# Attenuverting_Mixer_Slim_Front_Panel_v1.net
KiCad netlist of a schematic drawn in EAGLE
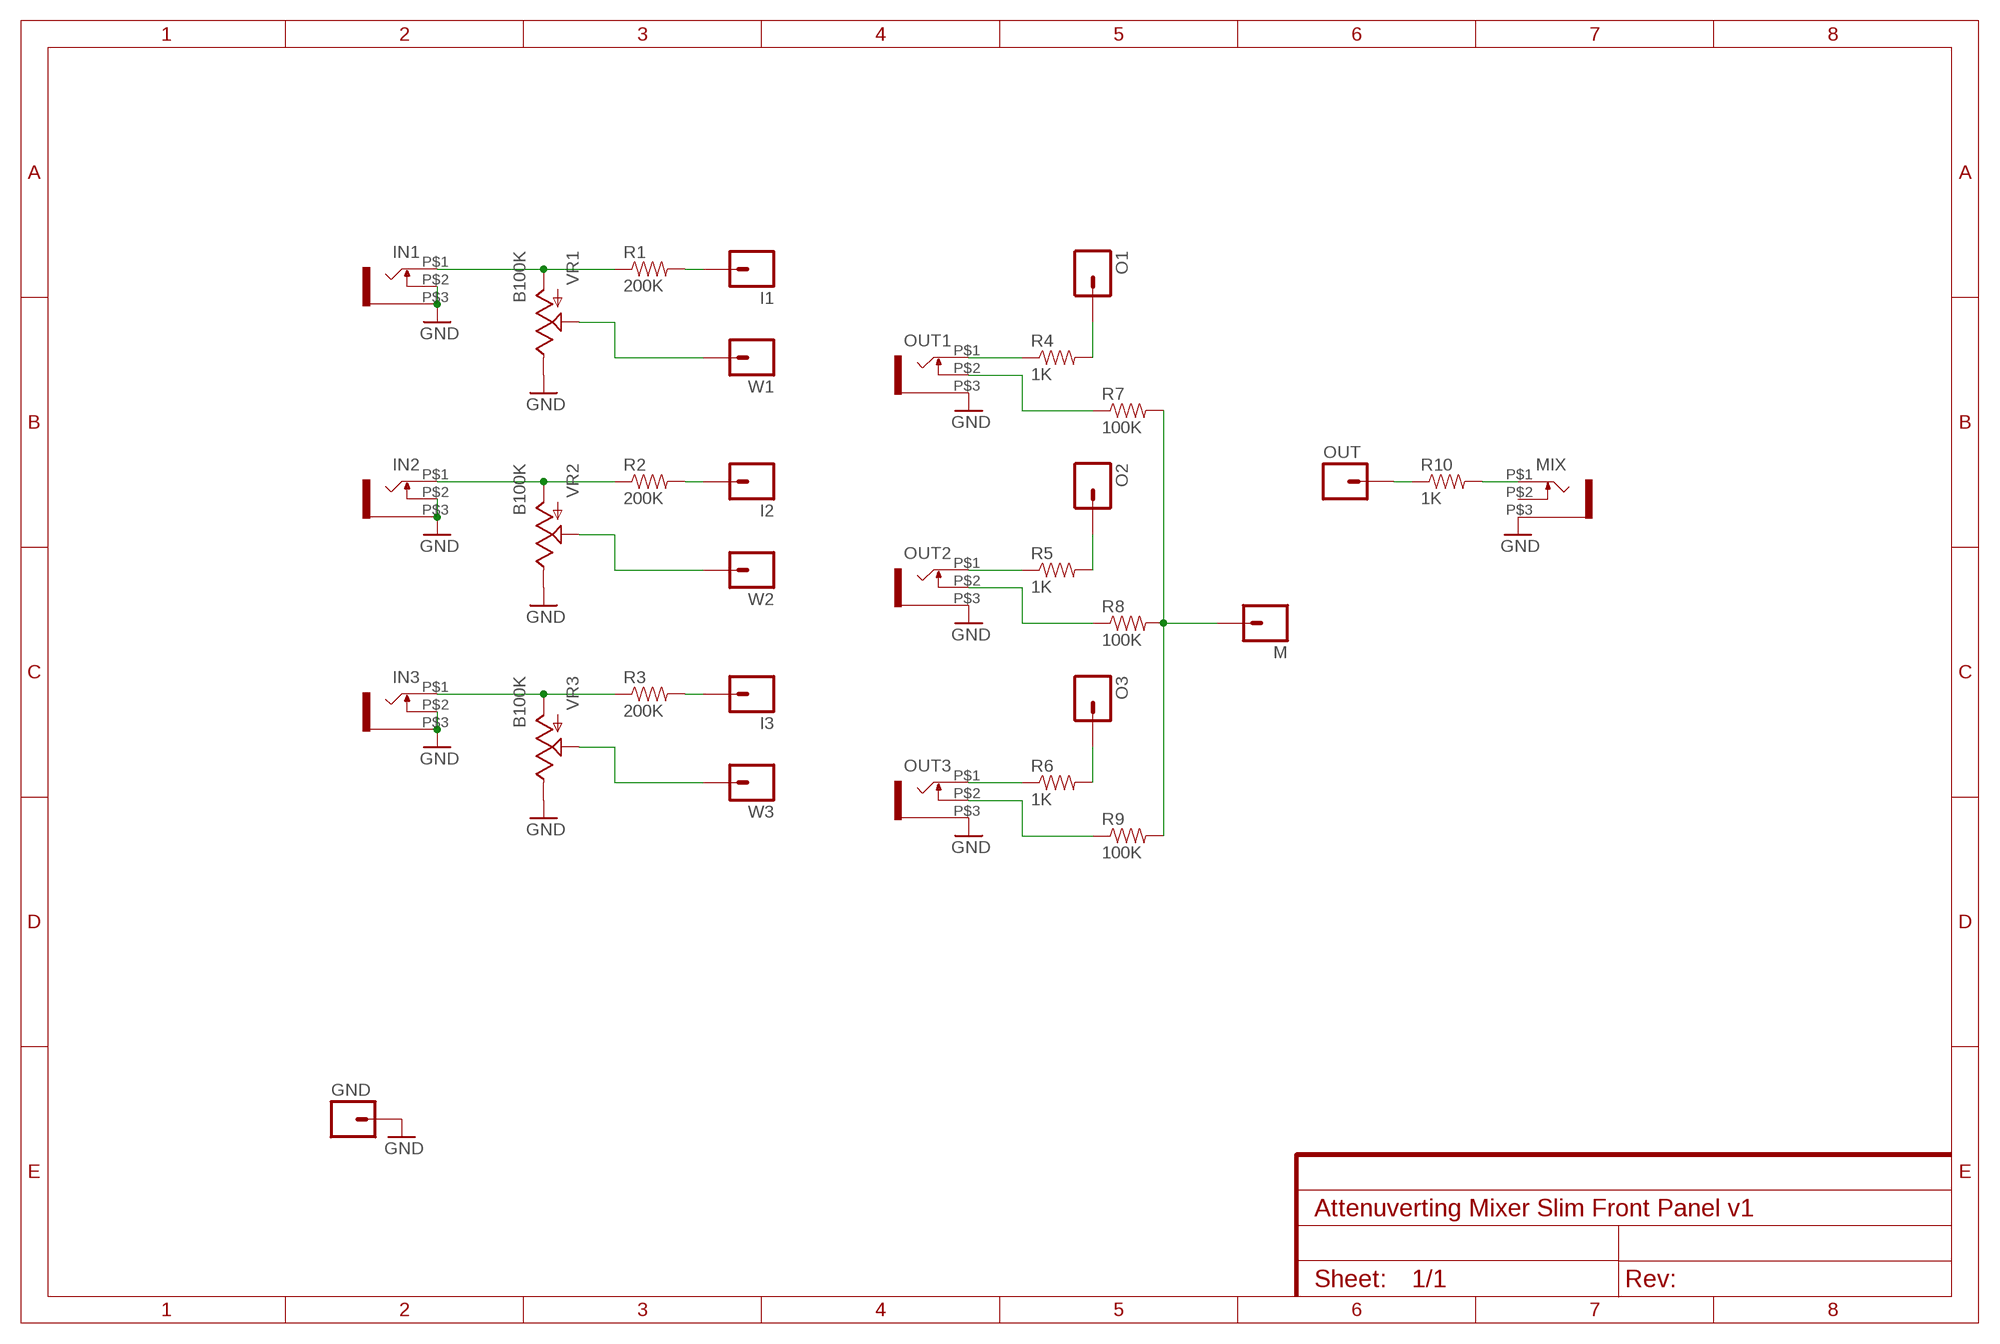
[diagram p0: schematic, sheet 1]

(export (version "E")
  (design (tool "Eeschema 10.0.6"))
  (components
    (comp (ref "GND")
      (value "M01PTH")
      (footprint "eagle-import:1X01")
      (libsource (lib "eagle-import") (part "M01PTH"))
    )
    (comp (ref "I1")
      (value "M01PTH")
      (footprint "eagle-import:1X01")
      (libsource (lib "eagle-import") (part "M01PTH"))
    )
    (comp (ref "I2")
      (value "M01PTH")
      (footprint "eagle-import:1X01")
      (libsource (lib "eagle-import") (part "M01PTH"))
    )
    (comp (ref "I3")
      (value "M01PTH")
      (footprint "eagle-import:1X01")
      (libsource (lib "eagle-import") (part "M01PTH"))
    )
    (comp (ref "IN1")
      (value "WQP-PJ301M-12_JACK")
      (footprint "eagle-import:WQP-PJ301M-12_JACK")
      (libsource (lib "eagle-import") (part "WQP-PJ301M-12_JACK"))
    )
    (comp (ref "IN2")
      (value "WQP-PJ301M-12_JACK")
      (footprint "eagle-import:WQP-PJ301M-12_JACK")
      (libsource (lib "eagle-import") (part "WQP-PJ301M-12_JACK"))
    )
    (comp (ref "IN3")
      (value "WQP-PJ301M-12_JACK")
      (footprint "eagle-import:WQP-PJ301M-12_JACK")
      (libsource (lib "eagle-import") (part "WQP-PJ301M-12_JACK"))
    )
    (comp (ref "M")
      (value "M01PTH")
      (footprint "eagle-import:1X01")
      (libsource (lib "eagle-import") (part "M01PTH"))
    )
    (comp (ref "MIX")
      (value "WQP-PJ301M-12_JACK")
      (footprint "eagle-import:WQP-PJ301M-12_JACK")
      (libsource (lib "eagle-import") (part "WQP-PJ301M-12_JACK"))
    )
    (comp (ref "O1")
      (value "M01PTH")
      (footprint "eagle-import:1X01")
      (libsource (lib "eagle-import") (part "M01PTH"))
    )
    (comp (ref "O2")
      (value "M01PTH")
      (footprint "eagle-import:1X01")
      (libsource (lib "eagle-import") (part "M01PTH"))
    )
    (comp (ref "O3")
      (value "M01PTH")
      (footprint "eagle-import:1X01")
      (libsource (lib "eagle-import") (part "M01PTH"))
    )
    (comp (ref "OUT")
      (value "M01PTH")
      (footprint "eagle-import:1X01")
      (libsource (lib "eagle-import") (part "M01PTH"))
    )
    (comp (ref "OUT1")
      (value "WQP-PJ301M-12_JACK")
      (footprint "eagle-import:WQP-PJ301M-12_JACK")
      (libsource (lib "eagle-import") (part "WQP-PJ301M-12_JACK"))
    )
    (comp (ref "OUT2")
      (value "WQP-PJ301M-12_JACK")
      (footprint "eagle-import:WQP-PJ301M-12_JACK")
      (libsource (lib "eagle-import") (part "WQP-PJ301M-12_JACK"))
    )
    (comp (ref "OUT3")
      (value "WQP-PJ301M-12_JACK")
      (footprint "eagle-import:WQP-PJ301M-12_JACK")
      (libsource (lib "eagle-import") (part "WQP-PJ301M-12_JACK"))
    )
    (comp (ref "R1")
      (value "200K")
      (footprint "eagle-import:0805")
      (libsource (lib "eagle-import") (part "RESISTOR0805-RES"))
    )
    (comp (ref "R2")
      (value "200K")
      (footprint "eagle-import:0805")
      (libsource (lib "eagle-import") (part "RESISTOR0805-RES"))
    )
    (comp (ref "R3")
      (value "200K")
      (footprint "eagle-import:0805")
      (libsource (lib "eagle-import") (part "RESISTOR0805-RES"))
    )
    (comp (ref "R4")
      (value "1K")
      (footprint "eagle-import:0805")
      (libsource (lib "eagle-import") (part "RESISTOR0805-RES"))
    )
    (comp (ref "R5")
      (value "1K")
      (footprint "eagle-import:0805")
      (libsource (lib "eagle-import") (part "RESISTOR0805-RES"))
    )
    (comp (ref "R6")
      (value "1K")
      (footprint "eagle-import:0805")
      (libsource (lib "eagle-import") (part "RESISTOR0805-RES"))
    )
    (comp (ref "R7")
      (value "100K")
      (footprint "eagle-import:0805")
      (libsource (lib "eagle-import") (part "RESISTOR0805-RES"))
    )
    (comp (ref "R8")
      (value "100K")
      (footprint "eagle-import:0805")
      (libsource (lib "eagle-import") (part "RESISTOR0805-RES"))
    )
    (comp (ref "R9")
      (value "100K")
      (footprint "eagle-import:0805")
      (libsource (lib "eagle-import") (part "RESISTOR0805-RES"))
    )
    (comp (ref "R10")
      (value "1K")
      (footprint "eagle-import:0805")
      (libsource (lib "eagle-import") (part "RESISTOR0805-RES"))
    )
    (comp (ref "VR1")
      (value "B100K")
      (footprint "eagle-import:ALPS_POT")
      (libsource (lib "eagle-import") (part "POT"))
    )
    (comp (ref "VR2")
      (value "B100K")
      (footprint "eagle-import:ALPS_POT")
      (libsource (lib "eagle-import") (part "POT"))
    )
    (comp (ref "VR3")
      (value "B100K")
      (footprint "eagle-import:ALPS_POT")
      (libsource (lib "eagle-import") (part "POT"))
    )
    (comp (ref "W1")
      (value "M01PTH")
      (footprint "eagle-import:1X01")
      (libsource (lib "eagle-import") (part "M01PTH"))
    )
    (comp (ref "W2")
      (value "M01PTH")
      (footprint "eagle-import:1X01")
      (libsource (lib "eagle-import") (part "M01PTH"))
    )
    (comp (ref "W3")
      (value "M01PTH")
      (footprint "eagle-import:1X01")
      (libsource (lib "eagle-import") (part "M01PTH"))
    )
  )
  (nets
    (net (code "1") (name "GND") (class "Default")
      (node (ref "GND") (pin "1") (pinfunction "1_1") (pintype "passive"))
      (node (ref "IN1") (pin "P$2") (pinfunction "3_P$2") (pintype "passive"))
      (node (ref "IN1") (pin "P$3") (pinfunction "1_P$3") (pintype "passive"))
      (node (ref "IN2") (pin "P$2") (pinfunction "3_P$2") (pintype "passive"))
      (node (ref "IN2") (pin "P$3") (pinfunction "1_P$3") (pintype "passive"))
      (node (ref "IN3") (pin "P$2") (pinfunction "3_P$2") (pintype "passive"))
      (node (ref "IN3") (pin "P$3") (pinfunction "1_P$3") (pintype "passive"))
      (node (ref "MIX") (pin "P$3") (pinfunction "1_P$3") (pintype "passive"))
      (node (ref "OUT1") (pin "P$3") (pinfunction "1_P$3") (pintype "passive"))
      (node (ref "OUT2") (pin "P$3") (pinfunction "1_P$3") (pintype "passive"))
      (node (ref "OUT3") (pin "P$3") (pinfunction "1_P$3") (pintype "passive"))
      (node (ref "VR1") (pin "P$1") (pinfunction "E_P$1") (pintype "passive"))
      (node (ref "VR2") (pin "P$1") (pinfunction "E_P$1") (pintype "passive"))
      (node (ref "VR3") (pin "P$1") (pinfunction "E_P$1") (pintype "passive"))
    )
    (net (code "2") (name "Net-(I1-Pad1)") (class "Default")
      (node (ref "I1") (pin "1") (pinfunction "1_1") (pintype "passive"))
      (node (ref "R1") (pin "2") (pinfunction "2_2") (pintype "passive"))
    )
    (net (code "3") (name "Net-(I2-Pad1)") (class "Default")
      (node (ref "I2") (pin "1") (pinfunction "1_1") (pintype "passive"))
      (node (ref "R2") (pin "2") (pinfunction "2_2") (pintype "passive"))
    )
    (net (code "4") (name "Net-(I3-Pad1)") (class "Default")
      (node (ref "I3") (pin "1") (pinfunction "1_1") (pintype "passive"))
      (node (ref "R3") (pin "2") (pinfunction "2_2") (pintype "passive"))
    )
    (net (code "5") (name "Net-(IN1-2)") (class "Default")
      (node (ref "IN1") (pin "P$1") (pinfunction "2_P$1") (pintype "passive"))
      (node (ref "R1") (pin "1") (pinfunction "1_1") (pintype "passive"))
      (node (ref "VR1") (pin "P$3") (pinfunction "A_P$3") (pintype "passive"))
    )
    (net (code "6") (name "Net-(IN2-2)") (class "Default")
      (node (ref "IN2") (pin "P$1") (pinfunction "2_P$1") (pintype "passive"))
      (node (ref "R2") (pin "1") (pinfunction "1_1") (pintype "passive"))
      (node (ref "VR2") (pin "P$3") (pinfunction "A_P$3") (pintype "passive"))
    )
    (net (code "7") (name "Net-(IN3-2)") (class "Default")
      (node (ref "IN3") (pin "P$1") (pinfunction "2_P$1") (pintype "passive"))
      (node (ref "R3") (pin "1") (pinfunction "1_1") (pintype "passive"))
      (node (ref "VR3") (pin "P$3") (pinfunction "A_P$3") (pintype "passive"))
    )
    (net (code "8") (name "Net-(M-Pad1)") (class "Default")
      (node (ref "M") (pin "1") (pinfunction "1_1") (pintype "passive"))
      (node (ref "R7") (pin "2") (pinfunction "2_2") (pintype "passive"))
      (node (ref "R8") (pin "2") (pinfunction "2_2") (pintype "passive"))
      (node (ref "R9") (pin "2") (pinfunction "2_2") (pintype "passive"))
    )
    (net (code "9") (name "Net-(MIX-2)") (class "Default")
      (node (ref "MIX") (pin "P$1") (pinfunction "2_P$1") (pintype "passive"))
      (node (ref "R10") (pin "2") (pinfunction "2_2") (pintype "passive"))
    )
    (net (code "10") (name "Net-(O1-Pad1)") (class "Default")
      (node (ref "O1") (pin "1") (pinfunction "1_1") (pintype "passive"))
      (node (ref "R4") (pin "2") (pinfunction "2_2") (pintype "passive"))
    )
    (net (code "11") (name "Net-(O2-Pad1)") (class "Default")
      (node (ref "O2") (pin "1") (pinfunction "1_1") (pintype "passive"))
      (node (ref "R5") (pin "2") (pinfunction "2_2") (pintype "passive"))
    )
    (net (code "12") (name "Net-(O3-Pad1)") (class "Default")
      (node (ref "O3") (pin "1") (pinfunction "1_1") (pintype "passive"))
      (node (ref "R6") (pin "2") (pinfunction "2_2") (pintype "passive"))
    )
    (net (code "13") (name "Net-(OUT-Pad1)") (class "Default")
      (node (ref "OUT") (pin "1") (pinfunction "1_1") (pintype "passive"))
      (node (ref "R10") (pin "1") (pinfunction "1_1") (pintype "passive"))
    )
    (net (code "14") (name "Net-(OUT1-2)") (class "Default")
      (node (ref "OUT1") (pin "P$1") (pinfunction "2_P$1") (pintype "passive"))
      (node (ref "R4") (pin "1") (pinfunction "1_1") (pintype "passive"))
    )
    (net (code "15") (name "Net-(OUT1-3)") (class "Default")
      (node (ref "OUT1") (pin "P$2") (pinfunction "3_P$2") (pintype "passive"))
      (node (ref "R7") (pin "1") (pinfunction "1_1") (pintype "passive"))
    )
    (net (code "16") (name "Net-(OUT2-2)") (class "Default")
      (node (ref "OUT2") (pin "P$1") (pinfunction "2_P$1") (pintype "passive"))
      (node (ref "R5") (pin "1") (pinfunction "1_1") (pintype "passive"))
    )
    (net (code "17") (name "Net-(OUT2-3)") (class "Default")
      (node (ref "OUT2") (pin "P$2") (pinfunction "3_P$2") (pintype "passive"))
      (node (ref "R8") (pin "1") (pinfunction "1_1") (pintype "passive"))
    )
    (net (code "18") (name "Net-(OUT3-2)") (class "Default")
      (node (ref "OUT3") (pin "P$1") (pinfunction "2_P$1") (pintype "passive"))
      (node (ref "R6") (pin "1") (pinfunction "1_1") (pintype "passive"))
    )
    (net (code "19") (name "Net-(OUT3-3)") (class "Default")
      (node (ref "OUT3") (pin "P$2") (pinfunction "3_P$2") (pintype "passive"))
      (node (ref "R9") (pin "1") (pinfunction "1_1") (pintype "passive"))
    )
    (net (code "20") (name "Net-(VR1-S)") (class "Default")
      (node (ref "VR1") (pin "P$2") (pinfunction "S_P$2") (pintype "passive"))
      (node (ref "W1") (pin "1") (pinfunction "1_1") (pintype "passive"))
    )
    (net (code "21") (name "Net-(VR2-S)") (class "Default")
      (node (ref "VR2") (pin "P$2") (pinfunction "S_P$2") (pintype "passive"))
      (node (ref "W2") (pin "1") (pinfunction "1_1") (pintype "passive"))
    )
    (net (code "22") (name "Net-(VR3-S)") (class "Default")
      (node (ref "VR3") (pin "P$2") (pinfunction "S_P$2") (pintype "passive"))
      (node (ref "W3") (pin "1") (pinfunction "1_1") (pintype "passive"))
    )
    (net (code "23") (name "unconnected-(MIX-3-PadP$2)") (class "Default")
      (node (ref "MIX") (pin "P$2") (pinfunction "3_P$2") (pintype "passive"))
    )
  )
)
